# FootForceSensor_ver1_0.net
KiCad netlist of a schematic drawn in EAGLE
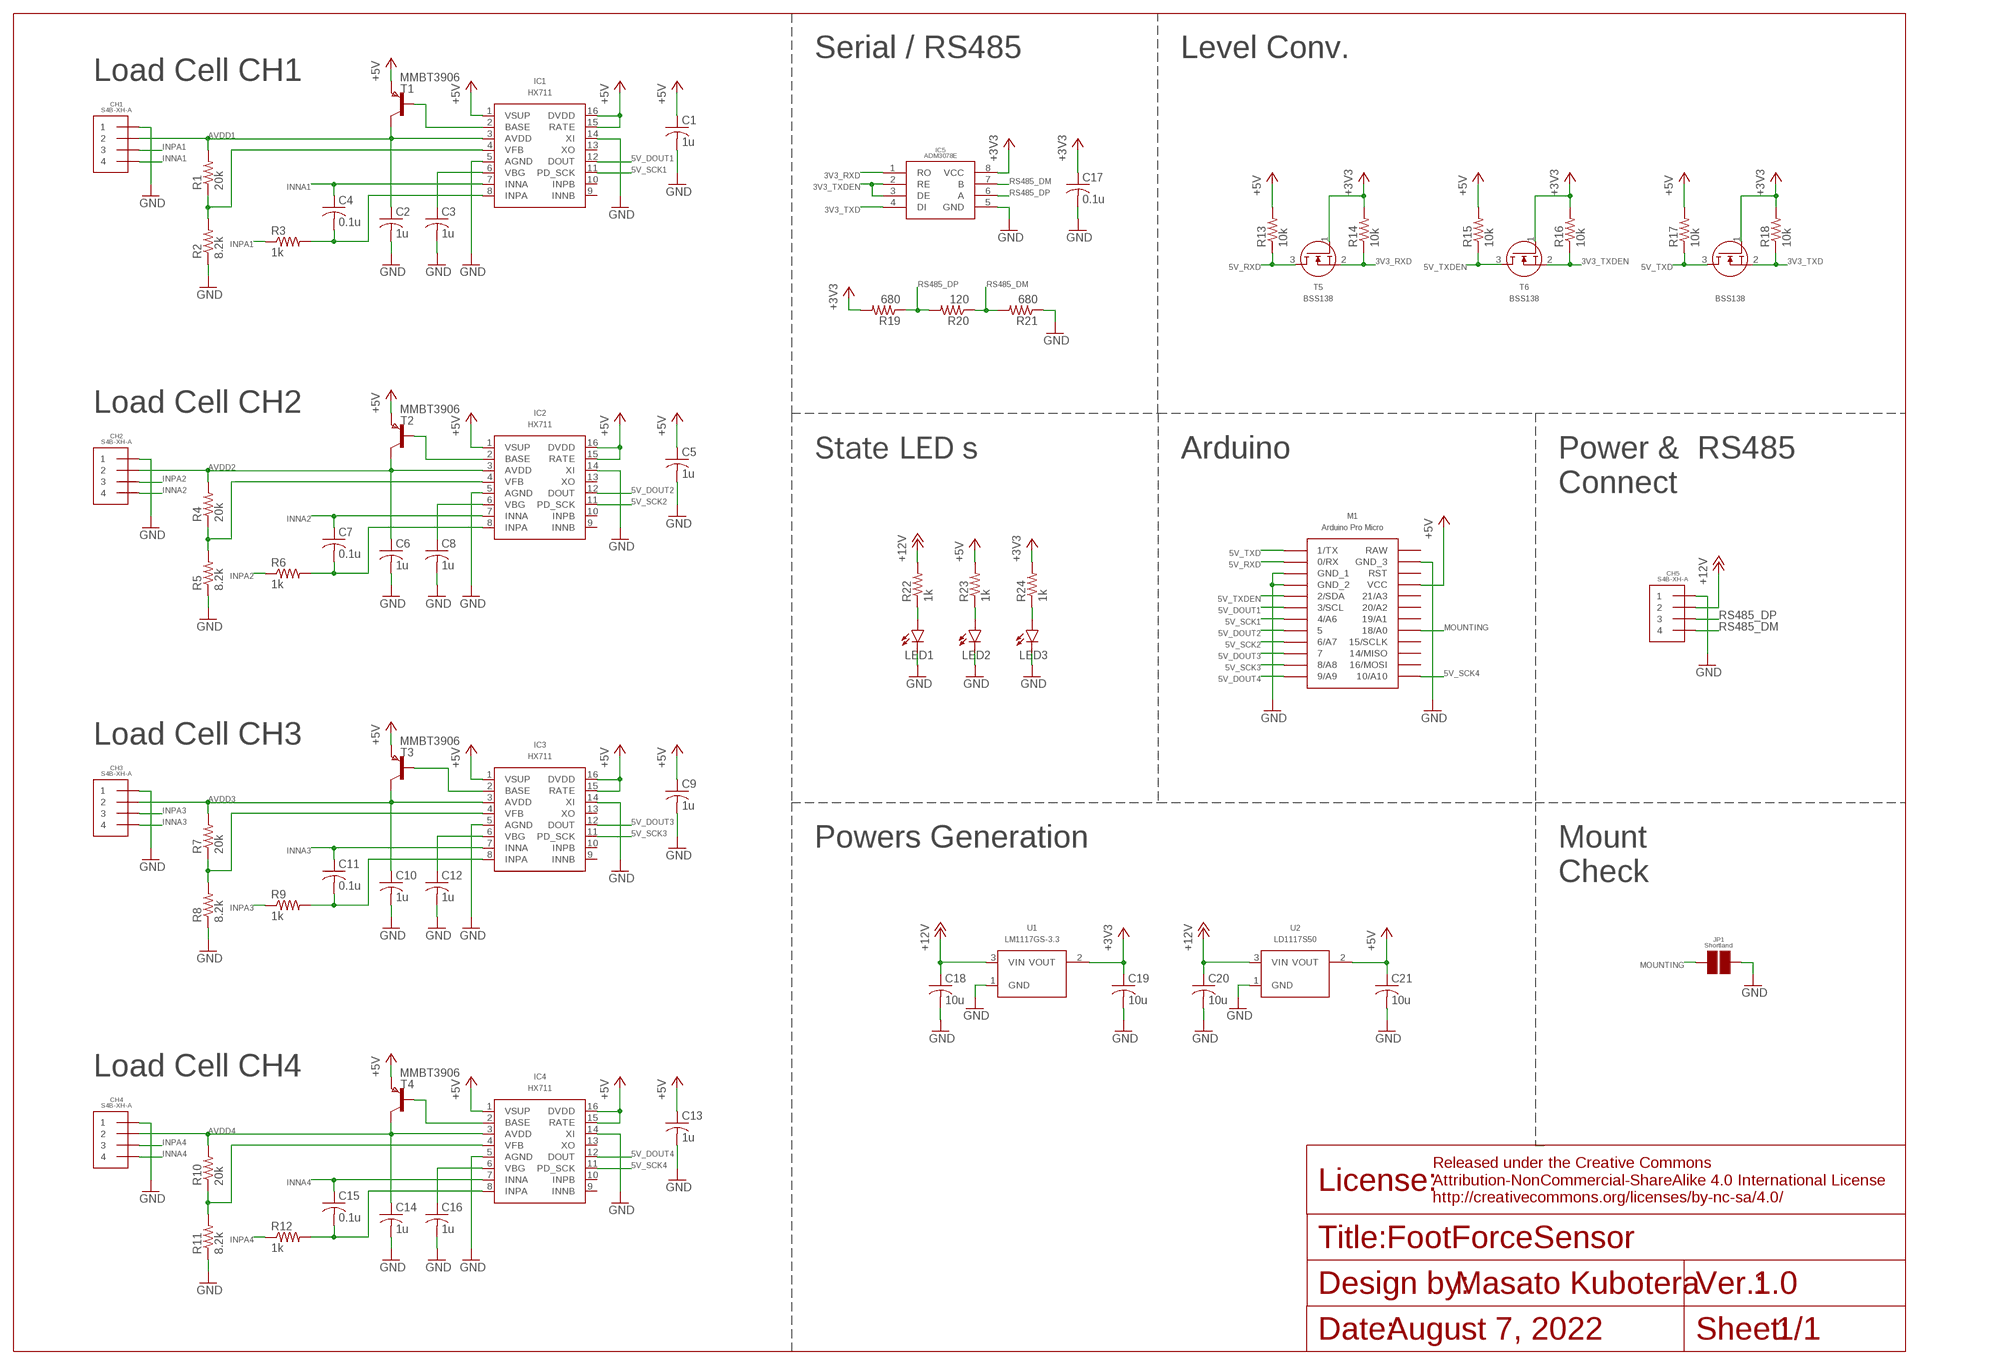
[diagram p0: schematic, sheet 1]

(export (version "E")
  (design (tool "Eeschema 10.0.6"))
  (components
    (comp (ref "C1")
      (value "1u")
      (footprint "eagle-import:C0603")
      (libsource (lib "eagle-import") (part "C-USC0603"))
    )
    (comp (ref "C2")
      (value "1u")
      (footprint "eagle-import:C0603")
      (libsource (lib "eagle-import") (part "C-USC0603"))
    )
    (comp (ref "C3")
      (value "1u")
      (footprint "eagle-import:C0603")
      (libsource (lib "eagle-import") (part "C-USC0603"))
    )
    (comp (ref "C4")
      (value "0.1u")
      (footprint "eagle-import:C0603")
      (libsource (lib "eagle-import") (part "C-USC0603"))
    )
    (comp (ref "C5")
      (value "1u")
      (footprint "eagle-import:C0603")
      (libsource (lib "eagle-import") (part "C-USC0603"))
    )
    (comp (ref "C6")
      (value "1u")
      (footprint "eagle-import:C0603")
      (libsource (lib "eagle-import") (part "C-USC0603"))
    )
    (comp (ref "C7")
      (value "0.1u")
      (footprint "eagle-import:C0603")
      (libsource (lib "eagle-import") (part "C-USC0603"))
    )
    (comp (ref "C8")
      (value "1u")
      (footprint "eagle-import:C0603")
      (libsource (lib "eagle-import") (part "C-USC0603"))
    )
    (comp (ref "C9")
      (value "1u")
      (footprint "eagle-import:C0603")
      (libsource (lib "eagle-import") (part "C-USC0603"))
    )
    (comp (ref "C10")
      (value "1u")
      (footprint "eagle-import:C0603")
      (libsource (lib "eagle-import") (part "C-USC0603"))
    )
    (comp (ref "C11")
      (value "0.1u")
      (footprint "eagle-import:C0603")
      (libsource (lib "eagle-import") (part "C-USC0603"))
    )
    (comp (ref "C12")
      (value "1u")
      (footprint "eagle-import:C0603")
      (libsource (lib "eagle-import") (part "C-USC0603"))
    )
    (comp (ref "C13")
      (value "1u")
      (footprint "eagle-import:C0603")
      (libsource (lib "eagle-import") (part "C-USC0603"))
    )
    (comp (ref "C14")
      (value "1u")
      (footprint "eagle-import:C0603")
      (libsource (lib "eagle-import") (part "C-USC0603"))
    )
    (comp (ref "C15")
      (value "0.1u")
      (footprint "eagle-import:C0603")
      (libsource (lib "eagle-import") (part "C-USC0603"))
    )
    (comp (ref "C16")
      (value "1u")
      (footprint "eagle-import:C0603")
      (libsource (lib "eagle-import") (part "C-USC0603"))
    )
    (comp (ref "C17")
      (value "0.1u")
      (footprint "eagle-import:C0603")
      (libsource (lib "eagle-import") (part "C-USC0603"))
    )
    (comp (ref "C18")
      (value "10u")
      (footprint "eagle-import:C0603")
      (libsource (lib "eagle-import") (part "C-USC0603"))
    )
    (comp (ref "C19")
      (value "10u")
      (footprint "eagle-import:C0603")
      (libsource (lib "eagle-import") (part "C-USC0603"))
    )
    (comp (ref "C20")
      (value "10u")
      (footprint "eagle-import:C0603")
      (libsource (lib "eagle-import") (part "C-USC0603"))
    )
    (comp (ref "C21")
      (value "10u")
      (footprint "eagle-import:C0603")
      (libsource (lib "eagle-import") (part "C-USC0603"))
    )
    (comp (ref "CH1")
      (value "S4B-XH-A")
      (footprint "eagle-import:S4B-XH-A")
      (libsource (lib "eagle-import") (part "S4B-XH-A"))
    )
    (comp (ref "CH2")
      (value "S4B-XH-A")
      (footprint "eagle-import:S4B-XH-A")
      (libsource (lib "eagle-import") (part "S4B-XH-A"))
    )
    (comp (ref "CH3")
      (value "S4B-XH-A")
      (footprint "eagle-import:S4B-XH-A")
      (libsource (lib "eagle-import") (part "S4B-XH-A"))
    )
    (comp (ref "CH4")
      (value "S4B-XH-A")
      (footprint "eagle-import:S4B-XH-A")
      (libsource (lib "eagle-import") (part "S4B-XH-A"))
    )
    (comp (ref "CH5")
      (value "S4B-XH-A")
      (footprint "eagle-import:S4B-XH-A")
      (libsource (lib "eagle-import") (part "S4B-XH-A"))
    )
    (comp (ref "IC1")
      (value "HX711")
      (footprint "eagle-import:HX711")
      (libsource (lib "eagle-import") (part "HX711"))
    )
    (comp (ref "IC2")
      (value "HX711")
      (footprint "eagle-import:HX711")
      (libsource (lib "eagle-import") (part "HX711"))
    )
    (comp (ref "IC3")
      (value "HX711")
      (footprint "eagle-import:HX711")
      (libsource (lib "eagle-import") (part "HX711"))
    )
    (comp (ref "IC4")
      (value "HX711")
      (footprint "eagle-import:HX711")
      (libsource (lib "eagle-import") (part "HX711"))
    )
    (comp (ref "IC5")
      (value "ADM3078E")
      (footprint "eagle-import:ADM3078E")
      (libsource (lib "eagle-import") (part "ADM3078E"))
    )
    (comp (ref "JP1")
      (value "SHORTLAND")
      (footprint "eagle-import:SHORTLAND")
      (libsource (lib "eagle-import") (part "SHORTLAND"))
    )
    (comp (ref "LED1")
      (value "LEDSML0603")
      (footprint "eagle-import:SML0603")
      (libsource (lib "eagle-import") (part "LEDSML0603"))
    )
    (comp (ref "LED2")
      (value "LEDSML0603")
      (footprint "eagle-import:SML0603")
      (libsource (lib "eagle-import") (part "LEDSML0603"))
    )
    (comp (ref "LED3")
      (value "LEDSML0603")
      (footprint "eagle-import:SML0603")
      (libsource (lib "eagle-import") (part "LEDSML0603"))
    )
    (comp (ref "M1")
      (value "PRO_MICRO_THROUGH_HOLE")
      (footprint "eagle-import:PRO_MICRO_THROUGH_HOLE")
      (libsource (lib "eagle-import") (part "PRO_MICRO_THROUGH_HOLE"))
    )
    (comp (ref "R1")
      (value "20k")
      (footprint "eagle-import:R0603")
      (libsource (lib "eagle-import") (part "R-US_R0603"))
    )
    (comp (ref "R2")
      (value "8.2k")
      (footprint "eagle-import:R0603")
      (libsource (lib "eagle-import") (part "R-US_R0603"))
    )
    (comp (ref "R3")
      (value "1k")
      (footprint "eagle-import:R0603")
      (libsource (lib "eagle-import") (part "R-US_R0603"))
    )
    (comp (ref "R4")
      (value "20k")
      (footprint "eagle-import:R0603")
      (libsource (lib "eagle-import") (part "R-US_R0603"))
    )
    (comp (ref "R5")
      (value "8.2k")
      (footprint "eagle-import:R0603")
      (libsource (lib "eagle-import") (part "R-US_R0603"))
    )
    (comp (ref "R6")
      (value "1k")
      (footprint "eagle-import:R0603")
      (libsource (lib "eagle-import") (part "R-US_R0603"))
    )
    (comp (ref "R7")
      (value "20k")
      (footprint "eagle-import:R0603")
      (libsource (lib "eagle-import") (part "R-US_R0603"))
    )
    (comp (ref "R8")
      (value "8.2k")
      (footprint "eagle-import:R0603")
      (libsource (lib "eagle-import") (part "R-US_R0603"))
    )
    (comp (ref "R9")
      (value "1k")
      (footprint "eagle-import:R0603")
      (libsource (lib "eagle-import") (part "R-US_R0603"))
    )
    (comp (ref "R10")
      (value "20k")
      (footprint "eagle-import:R0603")
      (libsource (lib "eagle-import") (part "R-US_R0603"))
    )
    (comp (ref "R11")
      (value "8.2k")
      (footprint "eagle-import:R0603")
      (libsource (lib "eagle-import") (part "R-US_R0603"))
    )
    (comp (ref "R12")
      (value "1k")
      (footprint "eagle-import:R0603")
      (libsource (lib "eagle-import") (part "R-US_R0603"))
    )
    (comp (ref "R13")
      (value "10k")
      (footprint "eagle-import:R0603")
      (libsource (lib "eagle-import") (part "R-US_R0603"))
    )
    (comp (ref "R14")
      (value "10k")
      (footprint "eagle-import:R0603")
      (libsource (lib "eagle-import") (part "R-US_R0603"))
    )
    (comp (ref "R15")
      (value "10k")
      (footprint "eagle-import:R0603")
      (libsource (lib "eagle-import") (part "R-US_R0603"))
    )
    (comp (ref "R16")
      (value "10k")
      (footprint "eagle-import:R0603")
      (libsource (lib "eagle-import") (part "R-US_R0603"))
    )
    (comp (ref "R17")
      (value "10k")
      (footprint "eagle-import:R0603")
      (libsource (lib "eagle-import") (part "R-US_R0603"))
    )
    (comp (ref "R18")
      (value "10k")
      (footprint "eagle-import:R0603")
      (libsource (lib "eagle-import") (part "R-US_R0603"))
    )
    (comp (ref "R19")
      (value "680")
      (footprint "eagle-import:R0603")
      (libsource (lib "eagle-import") (part "R-US_R0603"))
    )
    (comp (ref "R20")
      (value "120")
      (footprint "eagle-import:R0603")
      (libsource (lib "eagle-import") (part "R-US_R0603"))
    )
    (comp (ref "R21")
      (value "680")
      (footprint "eagle-import:R0603")
      (libsource (lib "eagle-import") (part "R-US_R0603"))
    )
    (comp (ref "R22")
      (value "1k")
      (footprint "eagle-import:R0603")
      (libsource (lib "eagle-import") (part "R-US_R0603"))
    )
    (comp (ref "R23")
      (value "1k")
      (footprint "eagle-import:R0603")
      (libsource (lib "eagle-import") (part "R-US_R0603"))
    )
    (comp (ref "R24")
      (value "1k")
      (footprint "eagle-import:R0603")
      (libsource (lib "eagle-import") (part "R-US_R0603"))
    )
    (comp (ref "T1")
      (value "MMBT3906")
      (footprint "eagle-import:SOT-23")
      (fields (field (name "MPN") "DSS20200L-7"))
      (libsource (lib "eagle-import") (part "PNPSOT23"))
    )
    (comp (ref "T2")
      (value "MMBT3906")
      (footprint "eagle-import:SOT-23")
      (fields (field (name "MPN") "DSS20200L-7"))
      (libsource (lib "eagle-import") (part "PNPSOT23"))
    )
    (comp (ref "T3")
      (value "MMBT3906")
      (footprint "eagle-import:SOT-23")
      (fields (field (name "MPN") "DSS20200L-7"))
      (libsource (lib "eagle-import") (part "PNPSOT23"))
    )
    (comp (ref "T4")
      (value "MMBT3906")
      (footprint "eagle-import:SOT-23")
      (fields (field (name "MPN") "DSS20200L-7"))
      (libsource (lib "eagle-import") (part "PNPSOT23"))
    )
    (comp (ref "T5")
      (value "BSS138")
      (footprint "eagle-import:BSS138")
      (libsource (lib "eagle-import") (part "BSS138"))
    )
    (comp (ref "T6")
      (value "BSS138")
      (footprint "eagle-import:BSS138")
      (libsource (lib "eagle-import") (part "BSS138"))
    )
    (comp (ref "T7")
      (value "BSS138")
      (footprint "eagle-import:BSS138")
      (libsource (lib "eagle-import") (part "BSS138"))
    )
    (comp (ref "U1")
      (value "LM1117GS-3.3")
      (footprint "eagle-import:SOT-223")
      (libsource (lib "eagle-import") (part "LM1117GS-3.3"))
    )
    (comp (ref "U2")
      (value "LD1117S50")
      (footprint "eagle-import:SOT-223")
      (libsource (lib "eagle-import") (part "LD1117S50"))
    )
  )
  (nets
    (net (code "1") (name "+3V3") (class "Default")
      (node (ref "C17") (pin "1") (pinfunction "1_1") (pintype "passive"))
      (node (ref "C19") (pin "1") (pinfunction "1_1") (pintype "passive"))
      (node (ref "IC5") (pin "8") (pinfunction "VCC_8") (pintype "bidirectional"))
      (node (ref "R14") (pin "2") (pinfunction "2_2") (pintype "passive"))
      (node (ref "R16") (pin "2") (pinfunction "2_2") (pintype "passive"))
      (node (ref "R18") (pin "2") (pinfunction "2_2") (pintype "passive"))
      (node (ref "R19") (pin "2") (pinfunction "2_2") (pintype "passive"))
      (node (ref "R24") (pin "2") (pinfunction "2_2") (pintype "passive"))
      (node (ref "T5") (pin "1") (pinfunction "G_1") (pintype "bidirectional"))
      (node (ref "T6") (pin "1") (pinfunction "G_1") (pintype "bidirectional"))
      (node (ref "T7") (pin "1") (pinfunction "G_1") (pintype "bidirectional"))
      (node (ref "U1") (pin "2") (pinfunction "VOUT_2") (pintype "bidirectional"))
    )
    (net (code "2") (name "+5V") (class "Default")
      (node (ref "C1") (pin "1") (pinfunction "1_1") (pintype "passive"))
      (node (ref "C13") (pin "1") (pinfunction "1_1") (pintype "passive"))
      (node (ref "C21") (pin "1") (pinfunction "1_1") (pintype "passive"))
      (node (ref "C5") (pin "1") (pinfunction "1_1") (pintype "passive"))
      (node (ref "C9") (pin "1") (pinfunction "1_1") (pintype "passive"))
      (node (ref "IC1") (pin "1") (pinfunction "VSUP_1") (pintype "bidirectional"))
      (node (ref "IC1") (pin "15") (pinfunction "RATE_15") (pintype "bidirectional"))
      (node (ref "IC1") (pin "16") (pinfunction "DVDD_16") (pintype "bidirectional"))
      (node (ref "IC2") (pin "1") (pinfunction "VSUP_1") (pintype "bidirectional"))
      (node (ref "IC2") (pin "15") (pinfunction "RATE_15") (pintype "bidirectional"))
      (node (ref "IC2") (pin "16") (pinfunction "DVDD_16") (pintype "bidirectional"))
      (node (ref "IC3") (pin "1") (pinfunction "VSUP_1") (pintype "bidirectional"))
      (node (ref "IC3") (pin "15") (pinfunction "RATE_15") (pintype "bidirectional"))
      (node (ref "IC3") (pin "16") (pinfunction "DVDD_16") (pintype "bidirectional"))
      (node (ref "IC4") (pin "1") (pinfunction "VSUP_1") (pintype "bidirectional"))
      (node (ref "IC4") (pin "15") (pinfunction "RATE_15") (pintype "bidirectional"))
      (node (ref "IC4") (pin "16") (pinfunction "DVDD_16") (pintype "bidirectional"))
      (node (ref "M1") (pin "VCC") (pinfunction "VCC_VCC") (pintype "bidirectional"))
      (node (ref "R13") (pin "2") (pinfunction "2_2") (pintype "passive"))
      (node (ref "R15") (pin "2") (pinfunction "2_2") (pintype "passive"))
      (node (ref "R17") (pin "2") (pinfunction "2_2") (pintype "passive"))
      (node (ref "R23") (pin "2") (pinfunction "2_2") (pintype "passive"))
      (node (ref "T1") (pin "2") (pinfunction "E_2") (pintype "passive"))
      (node (ref "T2") (pin "2") (pinfunction "E_2") (pintype "passive"))
      (node (ref "T3") (pin "2") (pinfunction "E_2") (pintype "passive"))
      (node (ref "T4") (pin "2") (pinfunction "E_2") (pintype "passive"))
      (node (ref "U2") (pin "2") (pinfunction "VOUT_2") (pintype "bidirectional"))
    )
    (net (code "3") (name "+12V") (class "Default")
      (node (ref "C18") (pin "1") (pinfunction "1_1") (pintype "passive"))
      (node (ref "C20") (pin "1") (pinfunction "1_1") (pintype "passive"))
      (node (ref "CH5") (pin "2") (pinfunction "2_2") (pintype "bidirectional"))
      (node (ref "R22") (pin "2") (pinfunction "2_2") (pintype "passive"))
      (node (ref "U1") (pin "3") (pinfunction "VIN_3") (pintype "bidirectional"))
      (node (ref "U2") (pin "3") (pinfunction "VIN_3") (pintype "bidirectional"))
    )
    (net (code "4") (name "/3V3_RXD") (class "Default")
      (node (ref "IC5") (pin "1") (pinfunction "RO_1") (pintype "bidirectional"))
      (node (ref "R14") (pin "1") (pinfunction "1_1") (pintype "passive"))
      (node (ref "T5") (pin "2") (pinfunction "S_2") (pintype "bidirectional"))
    )
    (net (code "5") (name "/3V3_TXD") (class "Default")
      (node (ref "IC5") (pin "4") (pinfunction "DI_4") (pintype "bidirectional"))
      (node (ref "R18") (pin "1") (pinfunction "1_1") (pintype "passive"))
      (node (ref "T7") (pin "2") (pinfunction "S_2") (pintype "bidirectional"))
    )
    (net (code "6") (name "/3V3_TXDEN") (class "Default")
      (node (ref "IC5") (pin "2") (pinfunction "RE_2") (pintype "bidirectional"))
      (node (ref "IC5") (pin "3") (pinfunction "DE_3") (pintype "bidirectional"))
      (node (ref "R16") (pin "1") (pinfunction "1_1") (pintype "passive"))
      (node (ref "T6") (pin "2") (pinfunction "S_2") (pintype "bidirectional"))
    )
    (net (code "7") (name "/5V_DOUT1") (class "Default")
      (node (ref "IC1") (pin "12") (pinfunction "DOUT_12") (pintype "bidirectional"))
      (node (ref "M1") (pin "3/SCL") (pinfunction "3/SCL_3/SCL") (pintype "bidirectional"))
    )
    (net (code "8") (name "/5V_DOUT2") (class "Default")
      (node (ref "IC2") (pin "12") (pinfunction "DOUT_12") (pintype "bidirectional"))
      (node (ref "M1") (pin "5") (pinfunction "5_5") (pintype "bidirectional"))
    )
    (net (code "9") (name "/5V_DOUT3") (class "Default")
      (node (ref "IC3") (pin "12") (pinfunction "DOUT_12") (pintype "bidirectional"))
      (node (ref "M1") (pin "7") (pinfunction "7_7") (pintype "bidirectional"))
    )
    (net (code "10") (name "/5V_DOUT4") (class "Default")
      (node (ref "IC4") (pin "12") (pinfunction "DOUT_12") (pintype "bidirectional"))
      (node (ref "M1") (pin "9/A9") (pinfunction "9/A9_9/A9") (pintype "bidirectional"))
    )
    (net (code "11") (name "/5V_RXD") (class "Default")
      (node (ref "M1") (pin "0/RX") (pinfunction "0/RX_0/RX") (pintype "bidirectional"))
      (node (ref "R13") (pin "1") (pinfunction "1_1") (pintype "passive"))
      (node (ref "T5") (pin "3") (pinfunction "D_3") (pintype "bidirectional"))
    )
    (net (code "12") (name "/5V_SCK1") (class "Default")
      (node (ref "IC1") (pin "11") (pinfunction "PD_SCK_11") (pintype "bidirectional"))
      (node (ref "M1") (pin "4/A6") (pinfunction "4/A6_4/A6") (pintype "bidirectional"))
    )
    (net (code "13") (name "/5V_SCK2") (class "Default")
      (node (ref "IC2") (pin "11") (pinfunction "PD_SCK_11") (pintype "bidirectional"))
      (node (ref "M1") (pin "6/A7") (pinfunction "6/A7_6/A7") (pintype "bidirectional"))
    )
    (net (code "14") (name "/5V_SCK3") (class "Default")
      (node (ref "IC3") (pin "11") (pinfunction "PD_SCK_11") (pintype "bidirectional"))
      (node (ref "M1") (pin "8/A8") (pinfunction "8/A8_8/A8") (pintype "bidirectional"))
    )
    (net (code "15") (name "/5V_SCK4") (class "Default")
      (node (ref "IC4") (pin "11") (pinfunction "PD_SCK_11") (pintype "bidirectional"))
      (node (ref "M1") (pin "10/A10") (pinfunction "10/A10_10/A10") (pintype "bidirectional"))
    )
    (net (code "16") (name "/5V_TXD") (class "Default")
      (node (ref "M1") (pin "1/TX") (pinfunction "1/TX_1/TX") (pintype "bidirectional"))
      (node (ref "R17") (pin "1") (pinfunction "1_1") (pintype "passive"))
      (node (ref "T7") (pin "3") (pinfunction "D_3") (pintype "bidirectional"))
    )
    (net (code "17") (name "/5V_TXDEN") (class "Default")
      (node (ref "M1") (pin "2/SDA") (pinfunction "2/SDA_2/SDA") (pintype "bidirectional"))
      (node (ref "R15") (pin "1") (pinfunction "1_1") (pintype "passive"))
      (node (ref "T6") (pin "3") (pinfunction "D_3") (pintype "bidirectional"))
    )
    (net (code "18") (name "/AVDD1") (class "Default")
      (node (ref "C2") (pin "1") (pinfunction "1_1") (pintype "passive"))
      (node (ref "CH1") (pin "2") (pinfunction "2_2") (pintype "bidirectional"))
      (node (ref "IC1") (pin "3") (pinfunction "AVDD_3") (pintype "bidirectional"))
      (node (ref "R1") (pin "2") (pinfunction "2_2") (pintype "passive"))
      (node (ref "T1") (pin "1") (pinfunction "C_1") (pintype "passive"))
    )
    (net (code "19") (name "/AVDD2") (class "Default")
      (node (ref "C6") (pin "1") (pinfunction "1_1") (pintype "passive"))
      (node (ref "CH2") (pin "2") (pinfunction "2_2") (pintype "bidirectional"))
      (node (ref "IC2") (pin "3") (pinfunction "AVDD_3") (pintype "bidirectional"))
      (node (ref "R4") (pin "2") (pinfunction "2_2") (pintype "passive"))
      (node (ref "T2") (pin "1") (pinfunction "C_1") (pintype "passive"))
    )
    (net (code "20") (name "/AVDD3") (class "Default")
      (node (ref "C10") (pin "1") (pinfunction "1_1") (pintype "passive"))
      (node (ref "CH3") (pin "2") (pinfunction "2_2") (pintype "bidirectional"))
      (node (ref "IC3") (pin "3") (pinfunction "AVDD_3") (pintype "bidirectional"))
      (node (ref "R7") (pin "2") (pinfunction "2_2") (pintype "passive"))
      (node (ref "T3") (pin "1") (pinfunction "C_1") (pintype "passive"))
    )
    (net (code "21") (name "/AVDD4") (class "Default")
      (node (ref "C14") (pin "1") (pinfunction "1_1") (pintype "passive"))
      (node (ref "CH4") (pin "2") (pinfunction "2_2") (pintype "bidirectional"))
      (node (ref "IC4") (pin "3") (pinfunction "AVDD_3") (pintype "bidirectional"))
      (node (ref "R10") (pin "2") (pinfunction "2_2") (pintype "passive"))
      (node (ref "T4") (pin "1") (pinfunction "C_1") (pintype "passive"))
    )
    (net (code "22") (name "/INNA1") (class "Default")
      (node (ref "C4") (pin "1") (pinfunction "1_1") (pintype "passive"))
      (node (ref "CH1") (pin "4") (pinfunction "4_4") (pintype "bidirectional"))
      (node (ref "IC1") (pin "7") (pinfunction "INNA_7") (pintype "bidirectional"))
    )
    (net (code "23") (name "/INNA2") (class "Default")
      (node (ref "C7") (pin "1") (pinfunction "1_1") (pintype "passive"))
      (node (ref "CH2") (pin "4") (pinfunction "4_4") (pintype "bidirectional"))
      (node (ref "IC2") (pin "7") (pinfunction "INNA_7") (pintype "bidirectional"))
    )
    (net (code "24") (name "/INNA3") (class "Default")
      (node (ref "C11") (pin "1") (pinfunction "1_1") (pintype "passive"))
      (node (ref "CH3") (pin "4") (pinfunction "4_4") (pintype "bidirectional"))
      (node (ref "IC3") (pin "7") (pinfunction "INNA_7") (pintype "bidirectional"))
    )
    (net (code "25") (name "/INNA4") (class "Default")
      (node (ref "C15") (pin "1") (pinfunction "1_1") (pintype "passive"))
      (node (ref "CH4") (pin "4") (pinfunction "4_4") (pintype "bidirectional"))
      (node (ref "IC4") (pin "7") (pinfunction "INNA_7") (pintype "bidirectional"))
    )
    (net (code "26") (name "/INPA1") (class "Default")
      (node (ref "CH1") (pin "3") (pinfunction "3_3") (pintype "bidirectional"))
      (node (ref "R3") (pin "1") (pinfunction "1_1") (pintype "passive"))
    )
    (net (code "27") (name "/INPA2") (class "Default")
      (node (ref "CH2") (pin "3") (pinfunction "3_3") (pintype "bidirectional"))
      (node (ref "R6") (pin "1") (pinfunction "1_1") (pintype "passive"))
    )
    (net (code "28") (name "/INPA3") (class "Default")
      (node (ref "CH3") (pin "3") (pinfunction "3_3") (pintype "bidirectional"))
      (node (ref "R9") (pin "1") (pinfunction "1_1") (pintype "passive"))
    )
    (net (code "29") (name "/INPA4") (class "Default")
      (node (ref "CH4") (pin "3") (pinfunction "3_3") (pintype "bidirectional"))
      (node (ref "R12") (pin "1") (pinfunction "1_1") (pintype "passive"))
    )
    (net (code "30") (name "/MOUNTING") (class "Default")
      (node (ref "JP1") (pin "1") (pinfunction "1_1") (pintype "bidirectional"))
      (node (ref "M1") (pin "18/A0") (pinfunction "18/A0_18/A0") (pintype "bidirectional"))
    )
    (net (code "31") (name "/RS485_DM") (class "Default")
      (node (ref "CH5") (pin "4") (pinfunction "4_4") (pintype "bidirectional"))
      (node (ref "IC5") (pin "7") (pinfunction "B_7") (pintype "bidirectional"))
      (node (ref "R20") (pin "1") (pinfunction "1_1") (pintype "passive"))
      (node (ref "R21") (pin "2") (pinfunction "2_2") (pintype "passive"))
    )
    (net (code "32") (name "/RS485_DP") (class "Default")
      (node (ref "CH5") (pin "3") (pinfunction "3_3") (pintype "bidirectional"))
      (node (ref "IC5") (pin "6") (pinfunction "A_6") (pintype "bidirectional"))
      (node (ref "R19") (pin "1") (pinfunction "1_1") (pintype "passive"))
      (node (ref "R20") (pin "2") (pinfunction "2_2") (pintype "passive"))
    )
    (net (code "33") (name "GND") (class "Default")
      (node (ref "C1") (pin "2") (pinfunction "2_2") (pintype "passive"))
      (node (ref "C10") (pin "2") (pinfunction "2_2") (pintype "passive"))
      (node (ref "C12") (pin "2") (pinfunction "2_2") (pintype "passive"))
      (node (ref "C13") (pin "2") (pinfunction "2_2") (pintype "passive"))
      (node (ref "C14") (pin "2") (pinfunction "2_2") (pintype "passive"))
      (node (ref "C16") (pin "2") (pinfunction "2_2") (pintype "passive"))
      (node (ref "C17") (pin "2") (pinfunction "2_2") (pintype "passive"))
      (node (ref "C18") (pin "2") (pinfunction "2_2") (pintype "passive"))
      (node (ref "C19") (pin "2") (pinfunction "2_2") (pintype "passive"))
      (node (ref "C2") (pin "2") (pinfunction "2_2") (pintype "passive"))
      (node (ref "C20") (pin "2") (pinfunction "2_2") (pintype "passive"))
      (node (ref "C21") (pin "2") (pinfunction "2_2") (pintype "passive"))
      (node (ref "C3") (pin "2") (pinfunction "2_2") (pintype "passive"))
      (node (ref "C5") (pin "2") (pinfunction "2_2") (pintype "passive"))
      (node (ref "C6") (pin "2") (pinfunction "2_2") (pintype "passive"))
      (node (ref "C8") (pin "2") (pinfunction "2_2") (pintype "passive"))
      (node (ref "C9") (pin "2") (pinfunction "2_2") (pintype "passive"))
      (node (ref "CH1") (pin "1") (pinfunction "1_1") (pintype "bidirectional"))
      (node (ref "CH2") (pin "1") (pinfunction "1_1") (pintype "bidirectional"))
      (node (ref "CH3") (pin "1") (pinfunction "1_1") (pintype "bidirectional"))
      (node (ref "CH4") (pin "1") (pinfunction "1_1") (pintype "bidirectional"))
      (node (ref "CH5") (pin "1") (pinfunction "1_1") (pintype "bidirectional"))
      (node (ref "IC1") (pin "14") (pinfunction "XI_14") (pintype "bidirectional"))
      (node (ref "IC1") (pin "5") (pinfunction "AGND_5") (pintype "bidirectional"))
      (node (ref "IC2") (pin "14") (pinfunction "XI_14") (pintype "bidirectional"))
      (node (ref "IC2") (pin "5") (pinfunction "AGND_5") (pintype "bidirectional"))
      (node (ref "IC3") (pin "14") (pinfunction "XI_14") (pintype "bidirectional"))
      (node (ref "IC3") (pin "5") (pinfunction "AGND_5") (pintype "bidirectional"))
      (node (ref "IC4") (pin "14") (pinfunction "XI_14") (pintype "bidirectional"))
      (node (ref "IC4") (pin "5") (pinfunction "AGND_5") (pintype "bidirectional"))
      (node (ref "IC5") (pin "5") (pinfunction "GND_5") (pintype "bidirectional"))
      (node (ref "JP1") (pin "2") (pinfunction "2_2") (pintype "bidirectional"))
      (node (ref "LED1") (pin "C") (pinfunction "C_C") (pintype "passive"))
      (node (ref "LED2") (pin "C") (pinfunction "C_C") (pintype "passive"))
      (node (ref "LED3") (pin "C") (pinfunction "C_C") (pintype "passive"))
      (node (ref "M1") (pin "GND_1") (pinfunction "GND_1_GND_1") (pintype "bidirectional"))
      (node (ref "M1") (pin "GND_2") (pinfunction "GND_2_GND_2") (pintype "bidirectional"))
      (node (ref "M1") (pin "GND_3") (pinfunction "GND_3_GND_3") (pintype "bidirectional"))
      (node (ref "R11") (pin "1") (pinfunction "1_1") (pintype "passive"))
      (node (ref "R2") (pin "1") (pinfunction "1_1") (pintype "passive"))
      (node (ref "R21") (pin "1") (pinfunction "1_1") (pintype "passive"))
      (node (ref "R5") (pin "1") (pinfunction "1_1") (pintype "passive"))
      (node (ref "R8") (pin "1") (pinfunction "1_1") (pintype "passive"))
      (node (ref "U1") (pin "1") (pinfunction "GND_1") (pintype "bidirectional"))
      (node (ref "U2") (pin "1") (pinfunction "GND_1") (pintype "bidirectional"))
    )
    (net (code "34") (name "Net-(IC1-BASE)") (class "Default")
      (node (ref "IC1") (pin "2") (pinfunction "BASE_2") (pintype "bidirectional"))
      (node (ref "T1") (pin "3") (pinfunction "B_3") (pintype "passive"))
    )
    (net (code "35") (name "Net-(IC1-INPA)") (class "Default")
      (node (ref "C4") (pin "2") (pinfunction "2_2") (pintype "passive"))
      (node (ref "IC1") (pin "8") (pinfunction "INPA_8") (pintype "bidirectional"))
      (node (ref "R3") (pin "2") (pinfunction "2_2") (pintype "passive"))
    )
    (net (code "36") (name "Net-(IC1-VBG)") (class "Default")
      (node (ref "C3") (pin "1") (pinfunction "1_1") (pintype "passive"))
      (node (ref "IC1") (pin "6") (pinfunction "VBG_6") (pintype "bidirectional"))
    )
    (net (code "37") (name "Net-(IC1-VFB)") (class "Default")
      (node (ref "IC1") (pin "4") (pinfunction "VFB_4") (pintype "bidirectional"))
      (node (ref "R1") (pin "1") (pinfunction "1_1") (pintype "passive"))
      (node (ref "R2") (pin "2") (pinfunction "2_2") (pintype "passive"))
    )
    (net (code "38") (name "Net-(IC2-BASE)") (class "Default")
      (node (ref "IC2") (pin "2") (pinfunction "BASE_2") (pintype "bidirectional"))
      (node (ref "T2") (pin "3") (pinfunction "B_3") (pintype "passive"))
    )
    (net (code "39") (name "Net-(IC2-INPA)") (class "Default")
      (node (ref "C7") (pin "2") (pinfunction "2_2") (pintype "passive"))
      (node (ref "IC2") (pin "8") (pinfunction "INPA_8") (pintype "bidirectional"))
      (node (ref "R6") (pin "2") (pinfunction "2_2") (pintype "passive"))
    )
    (net (code "40") (name "Net-(IC2-VBG)") (class "Default")
      (node (ref "C8") (pin "1") (pinfunction "1_1") (pintype "passive"))
      (node (ref "IC2") (pin "6") (pinfunction "VBG_6") (pintype "bidirectional"))
    )
    (net (code "41") (name "Net-(IC2-VFB)") (class "Default")
      (node (ref "IC2") (pin "4") (pinfunction "VFB_4") (pintype "bidirectional"))
      (node (ref "R4") (pin "1") (pinfunction "1_1") (pintype "passive"))
      (node (ref "R5") (pin "2") (pinfunction "2_2") (pintype "passive"))
    )
    (net (code "42") (name "Net-(IC3-BASE)") (class "Default")
      (node (ref "IC3") (pin "2") (pinfunction "BASE_2") (pintype "bidirectional"))
      (node (ref "T3") (pin "3") (pinfunction "B_3") (pintype "passive"))
    )
    (net (code "43") (name "Net-(IC3-INPA)") (class "Default")
      (node (ref "C11") (pin "2") (pinfunction "2_2") (pintype "passive"))
      (node (ref "IC3") (pin "8") (pinfunction "INPA_8") (pintype "bidirectional"))
      (node (ref "R9") (pin "2") (pinfunction "2_2") (pintype "passive"))
    )
    (net (code "44") (name "Net-(IC3-VBG)") (class "Default")
      (node (ref "C12") (pin "1") (pinfunction "1_1") (pintype "passive"))
      (node (ref "IC3") (pin "6") (pinfunction "VBG_6") (pintype "bidirectional"))
    )
    (net (code "45") (name "Net-(IC3-VFB)") (class "Default")
      (node (ref "IC3") (pin "4") (pinfunction "VFB_4") (pintype "bidirectional"))
      (node (ref "R7") (pin "1") (pinfunction "1_1") (pintype "passive"))
      (node (ref "R8") (pin "2") (pinfunction "2_2") (pintype "passive"))
    )
    (net (code "46") (name "Net-(IC4-BASE)") (class "Default")
      (node (ref "IC4") (pin "2") (pinfunction "BASE_2") (pintype "bidirectional"))
      (node (ref "T4") (pin "3") (pinfunction "B_3") (pintype "passive"))
    )
    (net (code "47") (name "Net-(IC4-INPA)") (class "Default")
      (node (ref "C15") (pin "2") (pinfunction "2_2") (pintype "passive"))
      (node (ref "IC4") (pin "8") (pinfunction "INPA_8") (pintype "bidirectional"))
      (node (ref "R12") (pin "2") (pinfunction "2_2") (pintype "passive"))
    )
    (net (code "48") (name "Net-(IC4-VBG)") (class "Default")
      (node (ref "C16") (pin "1") (pinfunction "1_1") (pintype "passive"))
      (node (ref "IC4") (pin "6") (pinfunction "VBG_6") (pintype "bidirectional"))
    )
    (net (code "49") (name "Net-(IC4-VFB)") (class "Default")
      (node (ref "IC4") (pin "4") (pinfunction "VFB_4") (pintype "bidirectional"))
      (node (ref "R10") (pin "1") (pinfunction "1_1") (pintype "passive"))
      (node (ref "R11") (pin "2") (pinfunction "2_2") (pintype "passive"))
    )
    (net (code "50") (name "Net-(LED1-PadA)") (class "Default")
      (node (ref "LED1") (pin "A") (pinfunction "A_A") (pintype "passive"))
      (node (ref "R22") (pin "1") (pinfunction "1_1") (pintype "passive"))
    )
    (net (code "51") (name "Net-(LED2-PadA)") (class "Default")
      (node (ref "LED2") (pin "A") (pinfunction "A_A") (pintype "passive"))
      (node (ref "R23") (pin "1") (pinfunction "1_1") (pintype "passive"))
    )
    (net (code "52") (name "Net-(LED3-PadA)") (class "Default")
      (node (ref "LED3") (pin "A") (pinfunction "A_A") (pintype "passive"))
      (node (ref "R24") (pin "1") (pinfunction "1_1") (pintype "passive"))
    )
    (net (code "53") (name "unconnected-(IC1-INNB-Pad9)") (class "Default")
      (node (ref "IC1") (pin "9") (pinfunction "INNB_9") (pintype "bidirectional"))
    )
    (net (code "54") (name "unconnected-(IC1-INPB-Pad10)") (class "Default")
      (node (ref "IC1") (pin "10") (pinfunction "INPB_10") (pintype "bidirectional"))
    )
    (net (code "55") (name "unconnected-(IC1-XO-Pad13)") (class "Default")
      (node (ref "IC1") (pin "13") (pinfunction "XO_13") (pintype "bidirectional"))
    )
    (net (code "56") (name "unconnected-(IC2-INNB-Pad9)") (class "Default")
      (node (ref "IC2") (pin "9") (pinfunction "INNB_9") (pintype "bidirectional"))
    )
    (net (code "57") (name "unconnected-(IC2-INPB-Pad10)") (class "Default")
      (node (ref "IC2") (pin "10") (pinfunction "INPB_10") (pintype "bidirectional"))
    )
    (net (code "58") (name "unconnected-(IC2-XO-Pad13)") (class "Default")
      (node (ref "IC2") (pin "13") (pinfunction "XO_13") (pintype "bidirectional"))
    )
    (net (code "59") (name "unconnected-(IC3-INNB-Pad9)") (class "Default")
      (node (ref "IC3") (pin "9") (pinfunction "INNB_9") (pintype "bidirectional"))
    )
    (net (code "60") (name "unconnected-(IC3-INPB-Pad10)") (class "Default")
      (node (ref "IC3") (pin "10") (pinfunction "INPB_10") (pintype "bidirectional"))
    )
    (net (code "61") (name "unconnected-(IC3-XO-Pad13)") (class "Default")
      (node (ref "IC3") (pin "13") (pinfunction "XO_13") (pintype "bidirectional"))
    )
    (net (code "62") (name "unconnected-(IC4-INNB-Pad9)") (class "Default")
      (node (ref "IC4") (pin "9") (pinfunction "INNB_9") (pintype "bidirectional"))
    )
    (net (code "63") (name "unconnected-(IC4-INPB-Pad10)") (class "Default")
      (node (ref "IC4") (pin "10") (pinfunction "INPB_10") (pintype "bidirectional"))
    )
    (net (code "64") (name "unconnected-(IC4-XO-Pad13)") (class "Default")
      (node (ref "IC4") (pin "13") (pinfunction "XO_13") (pintype "bidirectional"))
    )
    (net (code "65") (name "unconnected-(M1-16{slash}MOSI-Pad16_MOSI)") (class "Default")
      (node (ref "M1") (pin "16_MOSI") (pinfunction "16/MOSI_16_MOSI") (pintype "bidirectional"))
    )
    (net (code "66") (name "unconnected-(M1-Pad14{slash}MISO)") (class "Default")
      (node (ref "M1") (pin "14/MISO") (pinfunction "14/MISO_14/MISO") (pintype "bidirectional"))
    )
    (net (code "67") (name "unconnected-(M1-Pad15{slash}SCLK)") (class "Default")
      (node (ref "M1") (pin "15/SCLK") (pinfunction "15/SCLK_15/SCLK") (pintype "bidirectional"))
    )
    (net (code "68") (name "unconnected-(M1-Pad19{slash}A1)") (class "Default")
      (node (ref "M1") (pin "19/A1") (pinfunction "19/A1_19/A1") (pintype "bidirectional"))
    )
    (net (code "69") (name "unconnected-(M1-Pad20{slash}A2)") (class "Default")
      (node (ref "M1") (pin "20/A2") (pinfunction "20/A2_20/A2") (pintype "bidirectional"))
    )
    (net (code "70") (name "unconnected-(M1-Pad21{slash}A3)") (class "Default")
      (node (ref "M1") (pin "21/A3") (pinfunction "21/A3_21/A3") (pintype "bidirectional"))
    )
    (net (code "71") (name "unconnected-(M1-PadRAW)") (class "Default")
      (node (ref "M1") (pin "RAW") (pinfunction "RAW_RAW") (pintype "bidirectional"))
    )
    (net (code "72") (name "unconnected-(M1-PadRST)") (class "Default")
      (node (ref "M1") (pin "RST") (pinfunction "RST_RST") (pintype "bidirectional"))
    )
  )
)
